# bt-ir-blaster.net
KiCad netlist of a schematic drawn in EAGLE
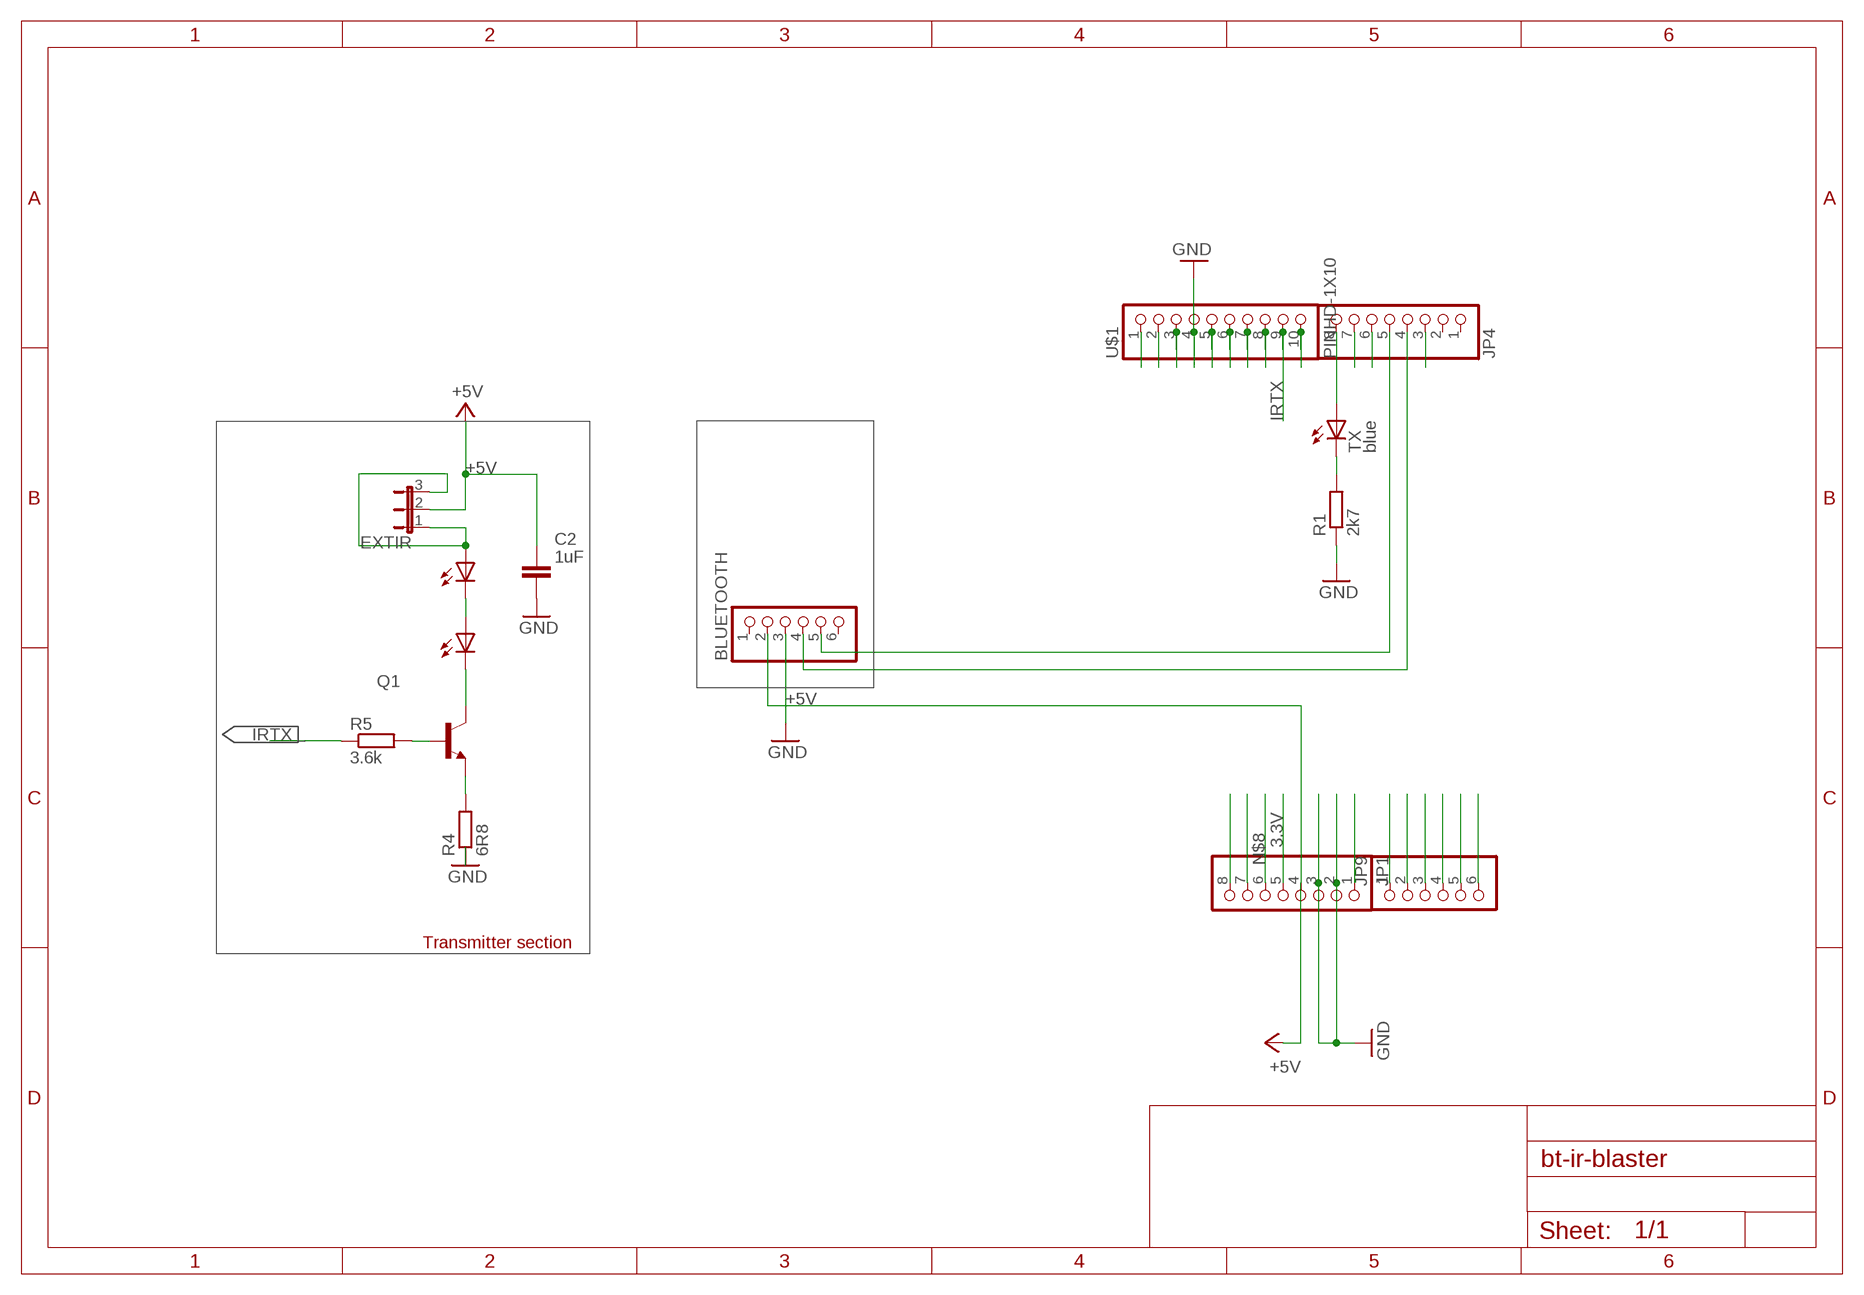
[diagram p0: schematic, sheet 1]

(export (version "E")
  (design (tool "Eeschema 10.0.6"))
  (components
    (comp (ref "BLUETOOTH")
      (value "PINHD-1X6")
      (footprint "eagle-import:1X06")
      (libsource (lib "eagle-import") (part "pinhead_PINHD-1X6"))
    )
    (comp (ref "C2")
      (value "1uF")
      (footprint "eagle-import:C603@1")
      (libsource (lib "eagle-import") (part "CAPACITOR_NPOL-0603"))
    )
    (comp (ref "EXTIR")
      (value "JP2E")
      (footprint "eagle-import:JP2")
      (libsource (lib "eagle-import") (part "JP2E"))
    )
    (comp (ref "JP1")
      (value "PINHD-1X8BIG")
      (footprint "eagle-import:1X08-BIG")
      (libsource (lib "eagle-import") (part "PINHD-1X8BIG"))
    )
    (comp (ref "JP4")
      (value "PINHD-1X8BIG")
      (footprint "eagle-import:1X08-BIG")
      (libsource (lib "eagle-import") (part "PINHD-1X8BIG"))
    )
    (comp (ref "JP9")
      (value "PINHD-1X6B")
      (footprint "eagle-import:1X06-BIG")
      (libsource (lib "eagle-import") (part "PINHD-1X6B"))
    )
    (comp (ref "Q1")
      (value "TRANSISTOR_BJT_NPN-SOT-23-BCE")
      (footprint "eagle-import:SOT-23")
      (libsource (lib "eagle-import") (part "TRANSISTOR_BJT_NPN-SOT-23-BCE"))
    )
    (comp (ref "R1")
      (value "2k7")
      (footprint "eagle-import:R0805")
      (libsource (lib "eagle-import") (part "R-EU_R0805"))
    )
    (comp (ref "R4")
      (value "6R8")
      (footprint "eagle-import:R1206")
      (libsource (lib "eagle-import") (part "R-EU_R1206"))
    )
    (comp (ref "R5")
      (value "3.6k")
      (footprint "eagle-import:R0603")
      (libsource (lib "eagle-import") (part "R-EU_R0603"))
    )
    (comp (ref "TX")
      (value "blue")
      (footprint "eagle-import:LED3MM")
      (libsource (lib "eagle-import") (part "LED3MM"))
    )
    (comp (ref "U$1")
      (value "PINHD-1X10")
      (footprint "eagle-import:1X10-BIG")
      (libsource (lib "eagle-import") (part "PINHD-1X10"))
    )
    (comp (ref "U$5")
      (value "IRLED5MM")
      (footprint "eagle-import:IRLED_HOLDER")
      (libsource (lib "eagle-import") (part "IRLED5MM"))
    )
    (comp (ref "U$7")
      (value "IRLED5MM")
      (footprint "eagle-import:IRLED_HOLDER")
      (libsource (lib "eagle-import") (part "IRLED5MM"))
    )
  )
  (nets
    (net (code "1") (name "+5V") (class "Default")
      (node (ref "BLUETOOTH") (pin "2") (pinfunction "2_2") (pintype "passive"))
      (node (ref "C2") (pin "1") (pinfunction "1_1") (pintype "passive"))
      (node (ref "EXTIR") (pin "2") (pinfunction "2_2") (pintype "passive"))
      (node (ref "JP1") (pin "4") (pinfunction "4_4") (pintype "passive"))
    )
    (net (code "2") (name "/3.3V") (class "Default")
      (node (ref "JP1") (pin "5") (pinfunction "5_5") (pintype "passive"))
    )
    (net (code "3") (name "/IRTX") (class "Default")
      (node (ref "R5") (pin "1") (pinfunction "1_1") (pintype "passive"))
      (node (ref "U$1") (pin "9") (pinfunction "9_9") (pintype "passive"))
    )
    (net (code "4") (name "/N$8") (class "Default")
      (node (ref "JP1") (pin "6") (pinfunction "6_6") (pintype "passive"))
    )
    (net (code "5") (name "GND") (class "Default")
      (node (ref "BLUETOOTH") (pin "3") (pinfunction "3_3") (pintype "passive"))
      (node (ref "C2") (pin "2") (pinfunction "2_2") (pintype "passive"))
      (node (ref "JP1") (pin "2") (pinfunction "2_2") (pintype "passive"))
      (node (ref "JP1") (pin "3") (pinfunction "3_3") (pintype "passive"))
      (node (ref "R1") (pin "1") (pinfunction "1_1") (pintype "passive"))
      (node (ref "R4") (pin "1") (pinfunction "1_1") (pintype "passive"))
      (node (ref "U$1") (pin "4") (pinfunction "4_4") (pintype "passive"))
    )
    (net (code "6") (name "Net-(BLUETOOTH-Pad4)") (class "Default")
      (node (ref "BLUETOOTH") (pin "4") (pinfunction "4_4") (pintype "passive"))
      (node (ref "JP4") (pin "4") (pinfunction "4_4") (pintype "passive"))
    )
    (net (code "7") (name "Net-(BLUETOOTH-Pad5)") (class "Default")
      (node (ref "BLUETOOTH") (pin "5") (pinfunction "5_5") (pintype "passive"))
      (node (ref "JP4") (pin "5") (pinfunction "5_5") (pintype "passive"))
    )
    (net (code "8") (name "Net-(EXTIR-Pad1)") (class "Default")
      (node (ref "EXTIR") (pin "1") (pinfunction "1_1") (pintype "passive"))
      (node (ref "EXTIR") (pin "3") (pinfunction "3_3") (pintype "passive"))
      (node (ref "U$7") (pin "A") (pinfunction "A_A") (pintype "passive"))
    )
    (net (code "9") (name "Net-(JP4-Pad8)") (class "Default")
      (node (ref "JP4") (pin "8") (pinfunction "8_8") (pintype "passive"))
      (node (ref "TX") (pin "A") (pinfunction "A_A") (pintype "passive"))
    )
    (net (code "10") (name "Net-(Q1-B)") (class "Default")
      (node (ref "Q1") (pin "1") (pinfunction "B_1") (pintype "passive"))
      (node (ref "R5") (pin "2") (pinfunction "2_2") (pintype "passive"))
    )
    (net (code "11") (name "Net-(Q1-C)") (class "Default")
      (node (ref "Q1") (pin "2") (pinfunction "C_2") (pintype "passive"))
      (node (ref "U$5") (pin "K") (pinfunction "C_K") (pintype "passive"))
    )
    (net (code "12") (name "Net-(Q1-E)") (class "Default")
      (node (ref "Q1") (pin "3") (pinfunction "E_3") (pintype "passive"))
      (node (ref "R4") (pin "2") (pinfunction "2_2") (pintype "passive"))
    )
    (net (code "13") (name "Net-(TX-C)") (class "Default")
      (node (ref "R1") (pin "2") (pinfunction "2_2") (pintype "passive"))
      (node (ref "TX") (pin "K") (pinfunction "C_K") (pintype "passive"))
    )
    (net (code "14") (name "Net-(U$7-C)") (class "Default")
      (node (ref "U$5") (pin "A") (pinfunction "A_A") (pintype "passive"))
      (node (ref "U$7") (pin "K") (pinfunction "C_K") (pintype "passive"))
    )
    (net (code "15") (name "unconnected-(BLUETOOTH-Pad1)") (class "Default")
      (node (ref "BLUETOOTH") (pin "1") (pinfunction "1_1") (pintype "passive"))
    )
    (net (code "16") (name "unconnected-(BLUETOOTH-Pad6)") (class "Default")
      (node (ref "BLUETOOTH") (pin "6") (pinfunction "6_6") (pintype "passive"))
    )
    (net (code "17") (name "unconnected-(JP1-Pad1)") (class "Default")
      (node (ref "JP1") (pin "1") (pinfunction "1_1") (pintype "passive"))
    )
    (net (code "18") (name "unconnected-(JP1-Pad7)") (class "Default")
      (node (ref "JP1") (pin "7") (pinfunction "7_7") (pintype "passive"))
    )
    (net (code "19") (name "unconnected-(JP1-Pad8)") (class "Default")
      (node (ref "JP1") (pin "8") (pinfunction "8_8") (pintype "passive"))
    )
    (net (code "20") (name "unconnected-(JP4-Pad1)") (class "Default")
      (node (ref "JP4") (pin "1") (pinfunction "1_1") (pintype "passive"))
    )
    (net (code "21") (name "unconnected-(JP4-Pad2)") (class "Default")
      (node (ref "JP4") (pin "2") (pinfunction "2_2") (pintype "passive"))
    )
    (net (code "22") (name "unconnected-(JP4-Pad3)") (class "Default")
      (node (ref "JP4") (pin "3") (pinfunction "3_3") (pintype "passive"))
    )
    (net (code "23") (name "unconnected-(JP4-Pad6)") (class "Default")
      (node (ref "JP4") (pin "6") (pinfunction "6_6") (pintype "passive"))
    )
    (net (code "24") (name "unconnected-(JP4-Pad7)") (class "Default")
      (node (ref "JP4") (pin "7") (pinfunction "7_7") (pintype "passive"))
    )
    (net (code "25") (name "unconnected-(JP9-Pad1)") (class "Default")
      (node (ref "JP9") (pin "1") (pinfunction "1_1") (pintype "passive"))
    )
    (net (code "26") (name "unconnected-(JP9-Pad2)") (class "Default")
      (node (ref "JP9") (pin "2") (pinfunction "2_2") (pintype "passive"))
    )
    (net (code "27") (name "unconnected-(JP9-Pad3)") (class "Default")
      (node (ref "JP9") (pin "3") (pinfunction "3_3") (pintype "passive"))
    )
    (net (code "28") (name "unconnected-(JP9-Pad4)") (class "Default")
      (node (ref "JP9") (pin "4") (pinfunction "4_4") (pintype "passive"))
    )
    (net (code "29") (name "unconnected-(JP9-Pad5)") (class "Default")
      (node (ref "JP9") (pin "5") (pinfunction "5_5") (pintype "passive"))
    )
    (net (code "30") (name "unconnected-(JP9-Pad6)") (class "Default")
      (node (ref "JP9") (pin "6") (pinfunction "6_6") (pintype "passive"))
    )
    (net (code "31") (name "unconnected-(U$1-Pad1)") (class "Default")
      (node (ref "U$1") (pin "1") (pinfunction "1_1") (pintype "passive"))
    )
    (net (code "32") (name "unconnected-(U$1-Pad2)") (class "Default")
      (node (ref "U$1") (pin "2") (pinfunction "2_2") (pintype "passive"))
    )
    (net (code "33") (name "unconnected-(U$1-Pad3)") (class "Default")
      (node (ref "U$1") (pin "3") (pinfunction "3_3") (pintype "passive"))
    )
    (net (code "34") (name "unconnected-(U$1-Pad5)") (class "Default")
      (node (ref "U$1") (pin "5") (pinfunction "5_5") (pintype "passive"))
    )
    (net (code "35") (name "unconnected-(U$1-Pad6)") (class "Default")
      (node (ref "U$1") (pin "6") (pinfunction "6_6") (pintype "passive"))
    )
    (net (code "36") (name "unconnected-(U$1-Pad7)") (class "Default")
      (node (ref "U$1") (pin "7") (pinfunction "7_7") (pintype "passive"))
    )
    (net (code "37") (name "unconnected-(U$1-Pad8)") (class "Default")
      (node (ref "U$1") (pin "8") (pinfunction "8_8") (pintype "passive"))
    )
    (net (code "38") (name "unconnected-(U$1-Pad10)") (class "Default")
      (node (ref "U$1") (pin "10") (pinfunction "10_10") (pintype "passive"))
    )
  )
)
